# Input_dig.net
KiCad netlist of a schematic drawn in Altium Designer
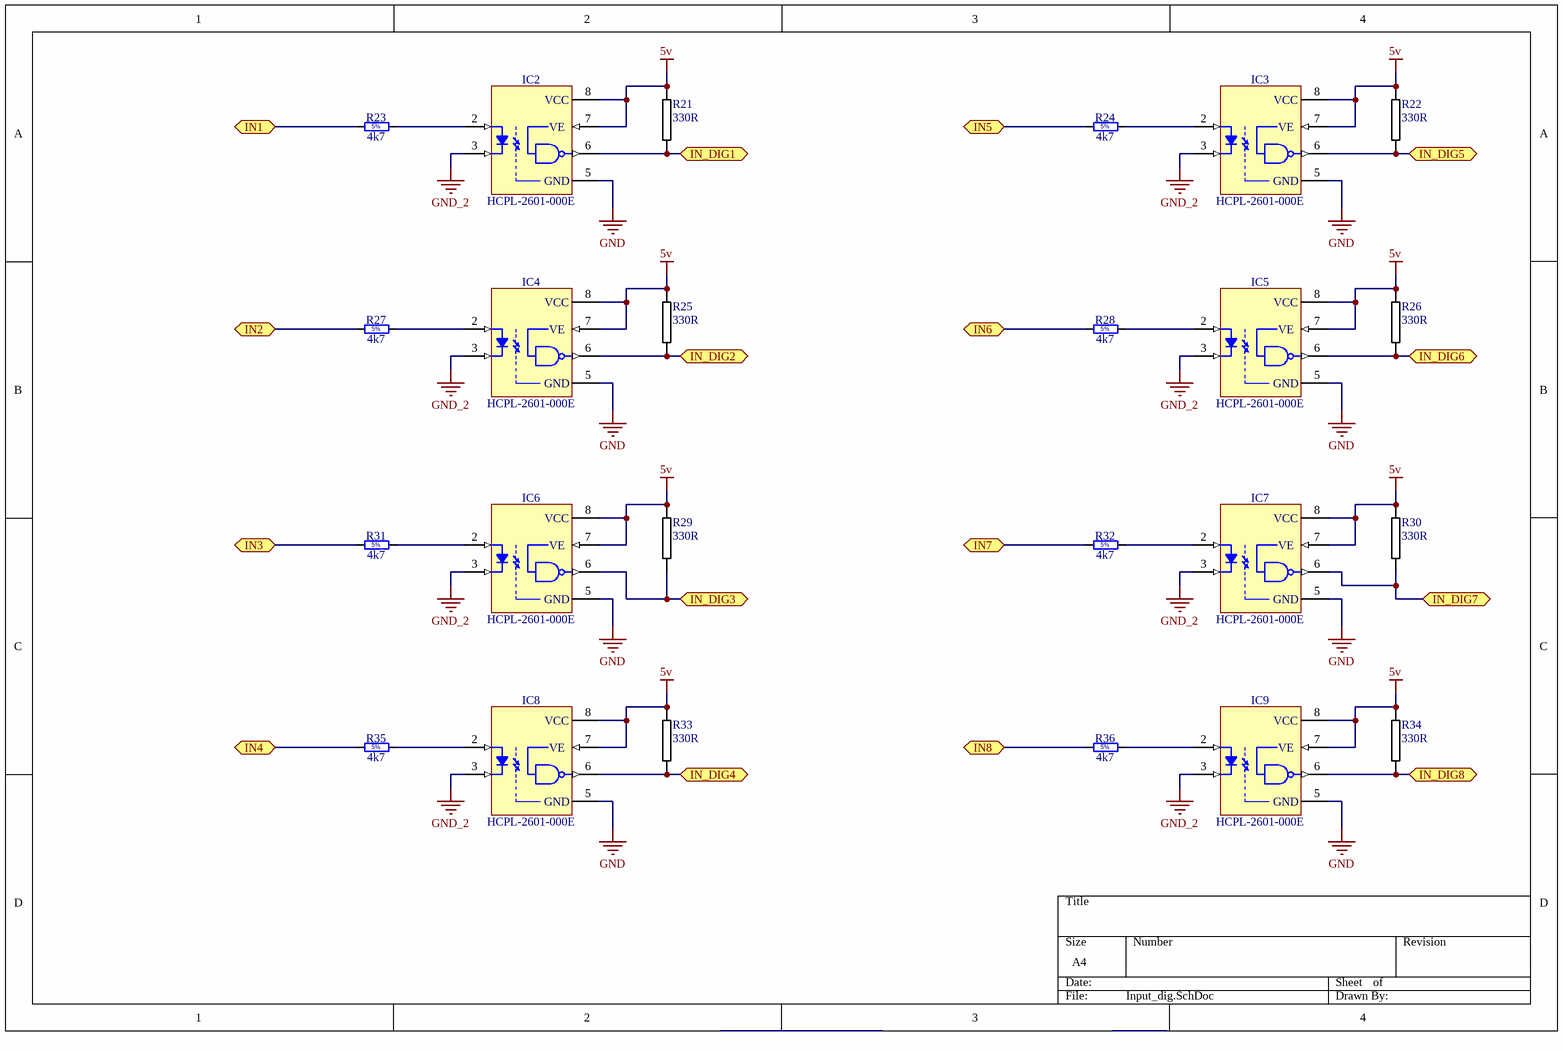
[diagram p0: Input_dig.SchDoc]

(export (version "E")
  (design (tool "Eeschema 10.0.6"))
  (components
    (comp (ref "IC2")
      (value "HCPL-2601-000E")
      (footprint "DIP8-300")
      (description "Single Optocoupler")
      (fields (field (name "MANUFACTURER") "AVAGO TECHNOLOGIES") (field (name "AUTHOR") "CERN DEM JLC"))
      (libsource (lib "ICs And Semiconductors") (part "Optocoupler Type8"))
    )
    (comp (ref "IC3")
      (value "HCPL-2601-000E")
      (footprint "DIP8-300")
      (description "Single Optocoupler")
      (fields (field (name "MANUFACTURER") "AVAGO TECHNOLOGIES") (field (name "AUTHOR") "CERN DEM JLC"))
      (libsource (lib "ICs And Semiconductors") (part "Optocoupler Type8"))
    )
    (comp (ref "IC4")
      (value "HCPL-2601-000E")
      (footprint "DIP8-300")
      (description "Single Optocoupler")
      (fields (field (name "MANUFACTURER") "AVAGO TECHNOLOGIES") (field (name "AUTHOR") "CERN DEM JLC"))
      (libsource (lib "ICs And Semiconductors") (part "Optocoupler Type8"))
    )
    (comp (ref "IC5")
      (value "HCPL-2601-000E")
      (footprint "DIP8-300")
      (description "Single Optocoupler")
      (fields (field (name "MANUFACTURER") "AVAGO TECHNOLOGIES") (field (name "AUTHOR") "CERN DEM JLC"))
      (libsource (lib "ICs And Semiconductors") (part "Optocoupler Type8"))
    )
    (comp (ref "IC6")
      (value "HCPL-2601-000E")
      (footprint "DIP8-300")
      (description "Single Optocoupler")
      (fields (field (name "MANUFACTURER") "AVAGO TECHNOLOGIES") (field (name "AUTHOR") "CERN DEM JLC"))
      (libsource (lib "ICs And Semiconductors") (part "Optocoupler Type8"))
    )
    (comp (ref "IC7")
      (value "HCPL-2601-000E")
      (footprint "DIP8-300")
      (description "Single Optocoupler")
      (fields (field (name "MANUFACTURER") "AVAGO TECHNOLOGIES") (field (name "AUTHOR") "CERN DEM JLC"))
      (libsource (lib "ICs And Semiconductors") (part "Optocoupler Type8"))
    )
    (comp (ref "IC8")
      (value "HCPL-2601-000E")
      (footprint "DIP8-300")
      (description "Single Optocoupler")
      (fields (field (name "MANUFACTURER") "AVAGO TECHNOLOGIES") (field (name "AUTHOR") "CERN DEM JLC"))
      (libsource (lib "ICs And Semiconductors") (part "Optocoupler Type8"))
    )
    (comp (ref "IC9")
      (value "HCPL-2601-000E")
      (footprint "DIP8-300")
      (description "Single Optocoupler")
      (fields (field (name "MANUFACTURER") "AVAGO TECHNOLOGIES") (field (name "AUTHOR") "CERN DEM JLC"))
      (libsource (lib "ICs And Semiconductors") (part "Optocoupler Type8"))
    )
    (comp (ref "R21")
      (value "330R")
      (footprint "0805R-330")
      (description "RESISTOR 0805 1/4 WATT THIN FILM")
      (libsource (lib "vh_altium_library") (part "0805R-330"))
    )
    (comp (ref "R22")
      (value "330R")
      (footprint "0805R-330")
      (description "RESISTOR 0805 1/4 WATT THIN FILM")
      (libsource (lib "vh_altium_library") (part "0805R-330"))
    )
    (comp (ref "R23")
      (value "4k7")
      (footprint "RES2286-1670X520")
      (description "Resistor - 5%")
      (fields
        (field (name "PART NUMBER") "RMF_4K7_5%_3W_250PPM_2286-1670X520")
        (field (name "POWER") "3W")
        (field (name "AUTHOR") "CERN DEM JLC")
      )
      (libsource (lib "Resistors") (part "Resistor - 5%"))
    )
    (comp (ref "R24")
      (value "4k7")
      (footprint "RES2286-1670X520")
      (description "Resistor - 5%")
      (fields
        (field (name "PART NUMBER") "RMF_4K7_5%_3W_250PPM_2286-1670X520")
        (field (name "POWER") "3W")
        (field (name "AUTHOR") "CERN DEM JLC")
      )
      (libsource (lib "Resistors") (part "Resistor - 5%"))
    )
    (comp (ref "R25")
      (value "330R")
      (footprint "0805R-330")
      (description "RESISTOR 0805 1/4 WATT THIN FILM")
      (libsource (lib "vh_altium_library") (part "0805R-330"))
    )
    (comp (ref "R26")
      (value "330R")
      (footprint "0805R-330")
      (description "RESISTOR 0805 1/4 WATT THIN FILM")
      (libsource (lib "vh_altium_library") (part "0805R-330"))
    )
    (comp (ref "R27")
      (value "4k7")
      (footprint "RES2286-1670X520")
      (description "Resistor - 5%")
      (fields
        (field (name "PART NUMBER") "RMF_4K7_5%_3W_250PPM_2286-1670X520")
        (field (name "POWER") "3W")
        (field (name "AUTHOR") "CERN DEM JLC")
      )
      (libsource (lib "Resistors") (part "Resistor - 5%"))
    )
    (comp (ref "R28")
      (value "4k7")
      (footprint "RES2286-1670X520")
      (description "Resistor - 5%")
      (fields
        (field (name "PART NUMBER") "RMF_4K7_5%_3W_250PPM_2286-1670X520")
        (field (name "POWER") "3W")
        (field (name "AUTHOR") "CERN DEM JLC")
      )
      (libsource (lib "Resistors") (part "Resistor - 5%"))
    )
    (comp (ref "R29")
      (value "330R")
      (footprint "0805R-330")
      (description "RESISTOR 0805 1/4 WATT THIN FILM")
      (libsource (lib "vh_altium_library") (part "0805R-330"))
    )
    (comp (ref "R30")
      (value "330R")
      (footprint "0805R-330")
      (description "RESISTOR 0805 1/4 WATT THIN FILM")
      (libsource (lib "vh_altium_library") (part "0805R-330"))
    )
    (comp (ref "R31")
      (value "4k7")
      (footprint "RES2286-1670X520")
      (description "Resistor - 5%")
      (fields
        (field (name "PART NUMBER") "RMF_4K7_5%_3W_250PPM_2286-1670X520")
        (field (name "POWER") "3W")
        (field (name "AUTHOR") "CERN DEM JLC")
      )
      (libsource (lib "Resistors") (part "Resistor - 5%"))
    )
    (comp (ref "R32")
      (value "4k7")
      (footprint "RES2286-1670X520")
      (description "Resistor - 5%")
      (fields
        (field (name "PART NUMBER") "RMF_4K7_5%_3W_250PPM_2286-1670X520")
        (field (name "POWER") "3W")
        (field (name "AUTHOR") "CERN DEM JLC")
      )
      (libsource (lib "Resistors") (part "Resistor - 5%"))
    )
    (comp (ref "R33")
      (value "330R")
      (footprint "0805R-330")
      (description "RESISTOR 0805 1/4 WATT THIN FILM")
      (libsource (lib "vh_altium_library") (part "0805R-330"))
    )
    (comp (ref "R34")
      (value "330R")
      (footprint "0805R-330")
      (description "RESISTOR 0805 1/4 WATT THIN FILM")
      (libsource (lib "vh_altium_library") (part "0805R-330"))
    )
    (comp (ref "R35")
      (value "4k7")
      (footprint "RES2286-1670X520")
      (description "Resistor - 5%")
      (fields
        (field (name "PART NUMBER") "RMF_4K7_5%_3W_250PPM_2286-1670X520")
        (field (name "POWER") "3W")
        (field (name "AUTHOR") "CERN DEM JLC")
      )
      (libsource (lib "Resistors") (part "Resistor - 5%"))
    )
    (comp (ref "R36")
      (value "4k7")
      (footprint "RES2286-1670X520")
      (description "Resistor - 5%")
      (fields
        (field (name "PART NUMBER") "RMF_4K7_5%_3W_250PPM_2286-1670X520")
        (field (name "POWER") "3W")
        (field (name "AUTHOR") "CERN DEM JLC")
      )
      (libsource (lib "Resistors") (part "Resistor - 5%"))
    )
  )
  (nets
    (net (code "1") (name "/IN1") (class "Default")
      (node (ref "R23") (pin "1") (pinfunction "1_1") (pintype "passive"))
    )
    (net (code "2") (name "/IN2") (class "Default")
      (node (ref "R27") (pin "1") (pinfunction "1_1") (pintype "passive"))
    )
    (net (code "3") (name "/IN3") (class "Default")
      (node (ref "R31") (pin "1") (pinfunction "1_1") (pintype "passive"))
    )
    (net (code "4") (name "/IN4") (class "Default")
      (node (ref "R35") (pin "1") (pinfunction "1_1") (pintype "passive"))
    )
    (net (code "5") (name "/IN5") (class "Default")
      (node (ref "R24") (pin "1") (pinfunction "1_1") (pintype "passive"))
    )
    (net (code "6") (name "/IN6") (class "Default")
      (node (ref "R28") (pin "1") (pinfunction "1_1") (pintype "passive"))
    )
    (net (code "7") (name "/IN7") (class "Default")
      (node (ref "R32") (pin "1") (pinfunction "1_1") (pintype "passive"))
    )
    (net (code "8") (name "/IN8") (class "Default")
      (node (ref "R36") (pin "1") (pinfunction "1_1") (pintype "passive"))
    )
    (net (code "9") (name "/IN_DIG1") (class "Default")
      (node (ref "IC2") (pin "6") (pinfunction "VO_6") (pintype "output"))
      (node (ref "R21") (pin "2") (pintype "passive"))
    )
    (net (code "10") (name "/IN_DIG2") (class "Default")
      (node (ref "IC4") (pin "6") (pinfunction "VO_6") (pintype "output"))
      (node (ref "R25") (pin "2") (pintype "passive"))
    )
    (net (code "11") (name "/IN_DIG3") (class "Default")
      (node (ref "IC6") (pin "6") (pinfunction "VO_6") (pintype "output"))
      (node (ref "R29") (pin "2") (pintype "passive"))
    )
    (net (code "12") (name "/IN_DIG4") (class "Default")
      (node (ref "IC8") (pin "6") (pinfunction "VO_6") (pintype "output"))
      (node (ref "R33") (pin "2") (pintype "passive"))
    )
    (net (code "13") (name "/IN_DIG5") (class "Default")
      (node (ref "IC3") (pin "6") (pinfunction "VO_6") (pintype "output"))
      (node (ref "R22") (pin "2") (pintype "passive"))
    )
    (net (code "14") (name "/IN_DIG6") (class "Default")
      (node (ref "IC5") (pin "6") (pinfunction "VO_6") (pintype "output"))
      (node (ref "R26") (pin "2") (pintype "passive"))
    )
    (net (code "15") (name "/IN_DIG7") (class "Default")
      (node (ref "IC7") (pin "6") (pinfunction "VO_6") (pintype "output"))
      (node (ref "R30") (pin "2") (pintype "passive"))
    )
    (net (code "16") (name "/IN_DIG8") (class "Default")
      (node (ref "IC9") (pin "6") (pinfunction "VO_6") (pintype "output"))
      (node (ref "R34") (pin "2") (pintype "passive"))
    )
    (net (code "17") (name "5v") (class "Default")
      (node (ref "IC2") (pin "7") (pinfunction "VE_7") (pintype "input"))
      (node (ref "IC2") (pin "8") (pinfunction "VCC_8") (pintype "power_in"))
      (node (ref "IC3") (pin "7") (pinfunction "VE_7") (pintype "input"))
      (node (ref "IC3") (pin "8") (pinfunction "VCC_8") (pintype "power_in"))
      (node (ref "IC4") (pin "7") (pinfunction "VE_7") (pintype "input"))
      (node (ref "IC4") (pin "8") (pinfunction "VCC_8") (pintype "power_in"))
      (node (ref "IC5") (pin "7") (pinfunction "VE_7") (pintype "input"))
      (node (ref "IC5") (pin "8") (pinfunction "VCC_8") (pintype "power_in"))
      (node (ref "IC6") (pin "7") (pinfunction "VE_7") (pintype "input"))
      (node (ref "IC6") (pin "8") (pinfunction "VCC_8") (pintype "power_in"))
      (node (ref "IC7") (pin "7") (pinfunction "VE_7") (pintype "input"))
      (node (ref "IC7") (pin "8") (pinfunction "VCC_8") (pintype "power_in"))
      (node (ref "IC8") (pin "7") (pinfunction "VE_7") (pintype "input"))
      (node (ref "IC8") (pin "8") (pinfunction "VCC_8") (pintype "power_in"))
      (node (ref "IC9") (pin "7") (pinfunction "VE_7") (pintype "input"))
      (node (ref "IC9") (pin "8") (pinfunction "VCC_8") (pintype "power_in"))
      (node (ref "R21") (pin "1") (pintype "passive"))
      (node (ref "R22") (pin "1") (pintype "passive"))
      (node (ref "R25") (pin "1") (pintype "passive"))
      (node (ref "R26") (pin "1") (pintype "passive"))
      (node (ref "R29") (pin "1") (pintype "passive"))
      (node (ref "R30") (pin "1") (pintype "passive"))
      (node (ref "R33") (pin "1") (pintype "passive"))
      (node (ref "R34") (pin "1") (pintype "passive"))
    )
    (net (code "18") (name "GND") (class "Default")
      (node (ref "IC2") (pin "5") (pinfunction "GND_5") (pintype "power_in"))
      (node (ref "IC3") (pin "5") (pinfunction "GND_5") (pintype "power_in"))
      (node (ref "IC4") (pin "5") (pinfunction "GND_5") (pintype "power_in"))
      (node (ref "IC5") (pin "5") (pinfunction "GND_5") (pintype "power_in"))
      (node (ref "IC6") (pin "5") (pinfunction "GND_5") (pintype "power_in"))
      (node (ref "IC7") (pin "5") (pinfunction "GND_5") (pintype "power_in"))
      (node (ref "IC8") (pin "5") (pinfunction "GND_5") (pintype "power_in"))
      (node (ref "IC9") (pin "5") (pinfunction "GND_5") (pintype "power_in"))
    )
    (net (code "19") (name "GND_2") (class "Default")
      (node (ref "IC2") (pin "3") (pinfunction "K_3") (pintype "input"))
      (node (ref "IC3") (pin "3") (pinfunction "K_3") (pintype "input"))
      (node (ref "IC4") (pin "3") (pinfunction "K_3") (pintype "input"))
      (node (ref "IC5") (pin "3") (pinfunction "K_3") (pintype "input"))
      (node (ref "IC6") (pin "3") (pinfunction "K_3") (pintype "input"))
      (node (ref "IC7") (pin "3") (pinfunction "K_3") (pintype "input"))
      (node (ref "IC8") (pin "3") (pinfunction "K_3") (pintype "input"))
      (node (ref "IC9") (pin "3") (pinfunction "K_3") (pintype "input"))
    )
    (net (code "20") (name "Net-(IC2-A)") (class "Default")
      (node (ref "IC2") (pin "2") (pinfunction "A_2") (pintype "input"))
      (node (ref "R23") (pin "2") (pinfunction "2_2") (pintype "passive"))
    )
    (net (code "21") (name "Net-(IC3-A)") (class "Default")
      (node (ref "IC3") (pin "2") (pinfunction "A_2") (pintype "input"))
      (node (ref "R24") (pin "2") (pinfunction "2_2") (pintype "passive"))
    )
    (net (code "22") (name "Net-(IC4-A)") (class "Default")
      (node (ref "IC4") (pin "2") (pinfunction "A_2") (pintype "input"))
      (node (ref "R27") (pin "2") (pinfunction "2_2") (pintype "passive"))
    )
    (net (code "23") (name "Net-(IC5-A)") (class "Default")
      (node (ref "IC5") (pin "2") (pinfunction "A_2") (pintype "input"))
      (node (ref "R28") (pin "2") (pinfunction "2_2") (pintype "passive"))
    )
    (net (code "24") (name "Net-(IC6-A)") (class "Default")
      (node (ref "IC6") (pin "2") (pinfunction "A_2") (pintype "input"))
      (node (ref "R31") (pin "2") (pinfunction "2_2") (pintype "passive"))
    )
    (net (code "25") (name "Net-(IC7-A)") (class "Default")
      (node (ref "IC7") (pin "2") (pinfunction "A_2") (pintype "input"))
      (node (ref "R32") (pin "2") (pinfunction "2_2") (pintype "passive"))
    )
    (net (code "26") (name "Net-(IC8-A)") (class "Default")
      (node (ref "IC8") (pin "2") (pinfunction "A_2") (pintype "input"))
      (node (ref "R35") (pin "2") (pinfunction "2_2") (pintype "passive"))
    )
    (net (code "27") (name "Net-(IC9-A)") (class "Default")
      (node (ref "IC9") (pin "2") (pinfunction "A_2") (pintype "input"))
      (node (ref "R36") (pin "2") (pinfunction "2_2") (pintype "passive"))
    )
  )
)
